# tinyarduinoschematic.net
KiCad netlist of a schematic drawn in Altium Designer
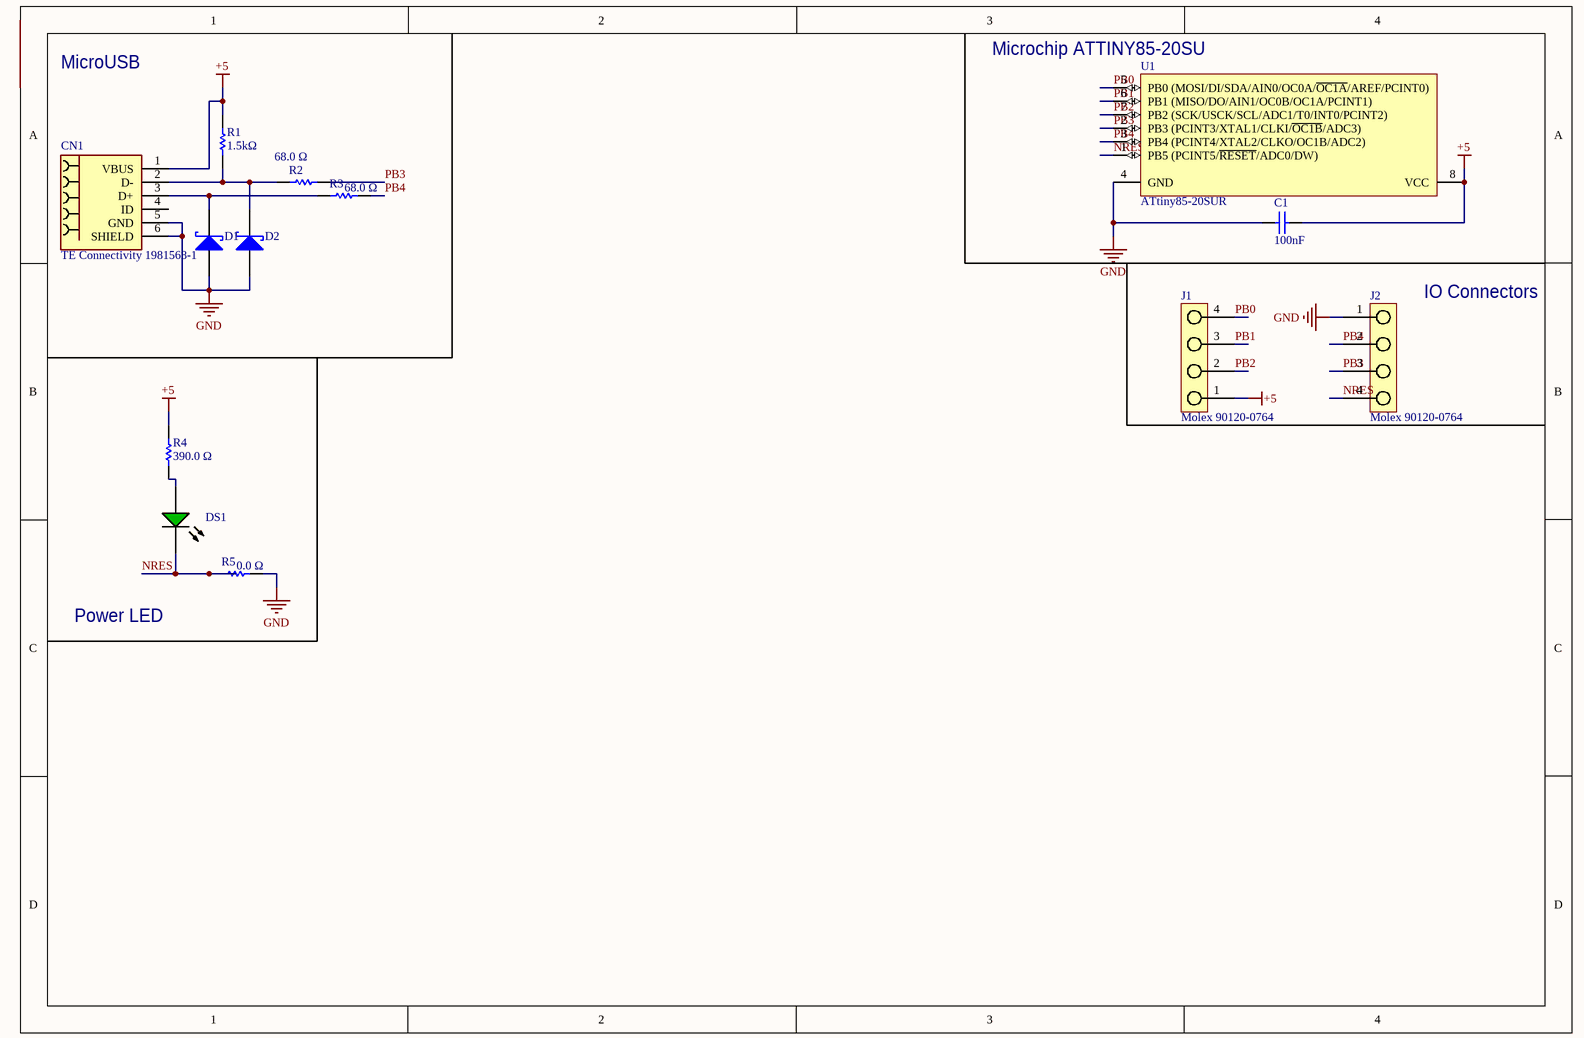
[diagram p0: tinyarduinoschematic.SchDoc]

(export (version "E")
  (design (tool "Eeschema 10.0.6"))
  (components
    (comp (ref "C1")
      (value "Cap")
      (footprint "PCB-cpn3sq1sqkb7wcygmy3s-1")
      (description "CAP CER 0.1UF 25V X7R 0603")
      (fields
        (field (name "CAPACITANCE") "100nF")
        (field (name "TOLERANCE") "±10%")
        (field (name "MANUFACTURER PART NUMBER") "06033C104KAT2A")
      )
      (libsource (lib "CommunityVault") (part "CMP-126693-6"))
    )
    (comp (ref "CN1")
      (value "TE Connectivity 1981568-1")
      (footprint "PCB-flraprbq3lplkrvccqj1-1")
      (description "Conn Micro USB 2.0 Type B RCP 5 POS 0.65mm Solder RA SMD 5 Terminal 1 Port T/R")
      (fields (field (name "MANUFACTURER PART NUMBER") "1981568-1"))
      (libsource (lib "CommunityVault") (part "CMP-c4780fb744281bbf-1"))
    )
    (comp (ref "D1")
      (value "Diodes Inc. B0540WS-7")
      (footprint "PCB-6tqbiewd2diqb4h5r69p-1")
      (description "B0540WS Series 40 V 0.5 A Schottky Barrier Rectifier Surface Mount - SOD-323")
      (fields (field (name "MANUFACTURER PART NUMBER") "B0540WS-7"))
      (libsource (lib "CommunityVault") (part "CMP-992e5020441546e9-1"))
    )
    (comp (ref "D2")
      (value "Diodes Inc. B0540WS-7")
      (footprint "PCB-6tqbiewd2diqb4h5r69p-1")
      (description "B0540WS Series 40 V 0.5 A Schottky Barrier Rectifier Surface Mount - SOD-323")
      (fields (field (name "MANUFACTURER PART NUMBER") "B0540WS-7"))
      (libsource (lib "CommunityVault") (part "CMP-992e5020441546e9-1"))
    )
    (comp (ref "DS1")
      (value "Avago HSMG-C190")
      (footprint "AVAG-HSMX-C190")
      (description "LED 570NM GREEN DIFF 0603 SMD")
      (libsource (lib "CommunityVault") (part "CMP-1544977-3"))
    )
    (comp (ref "J1")
      (value "Molex 90120-0764")
      (footprint "PCB-mruwntkvy73mrw75dg9m-1")
      (fields (field (name "MANUFACTURER PART NUMBER") "90120-0764"))
      (libsource (lib "") (part "SYM-f5c93cc9d0ed2a0e-2_1"))
    )
    (comp (ref "J2")
      (value "Molex 90120-0764")
      (footprint "PCB-mruwntkvy73mrw75dg9m-1")
      (fields (field (name "MANUFACTURER PART NUMBER") "90120-0764"))
      (libsource (lib "Octopart library") (part "SYM-f5c93cc9d0ed2a0e-2"))
    )
    (comp (ref "R1")
      (value "Vishay Dale CRCW06031K50JNEA")
      (footprint "RESC1609X50X30LL10T20")
      (description "RES SMD 1.5K OHM 5% 1/10W 0603")
      (fields (field (name "RESISTANCE") "1.5kΩ"))
      (libsource (lib "CommunityVault") (part "CMP-1856103-2"))
    )
    (comp (ref "R2")
      (value "Vishay Dale CRCW060368R0JNEA")
      (footprint "RESC1609X50X30ML10T20")
      (description "RES SMD 68 OHM 5% 1/10W 0603")
      (fields (field (name "RESISTANCE") "68.0 Ω"))
      (libsource (lib "CommunityVault") (part "CMP-1866767-2"))
    )
    (comp (ref "R3")
      (value "Vishay Dale CRCW060368R0JNEA")
      (footprint "RESC1609X50X30ML10T20")
      (description "RES SMD 68 OHM 5% 1/10W 0603")
      (fields (field (name "RESISTANCE") "68.0 Ω"))
      (libsource (lib "CommunityVault") (part "CMP-1866767-2"))
    )
    (comp (ref "R4")
      (value "Vishay Dale CRCW0603390RFKEA")
      (footprint "RESC1609X50X30LL10T20")
      (description "RES SMD 390 OHM 1% 1/10W 0603")
      (fields (field (name "RESISTANCE") "390.0 Ω"))
      (libsource (lib "CommunityVault") (part "CMP-3855866-2"))
    )
    (comp (ref "R5")
      (value "Vishay Dale CRCW06030000Z0EB")
      (footprint "RESC1609X50X30LL10T20")
      (description "Thick Film Resistors - SMD 1/10watt ZEROohm Jumper")
      (fields (field (name "RESISTANCE") "0.0 Ω"))
      (libsource (lib "CommunityVault") (part "CMP-1906891-2"))
    )
    (comp (ref "U1")
      (value "ATtiny85-20SUR")
      (footprint "8S2_L")
      (libsource (lib "Octopart library") (part "MC-8B-ATT25-IL8"))
    )
  )
  (nets
    (net (code "1") (name "+5") (class "Default")
      (node (ref "C1") (pin "1") (pinfunction "1_1") (pintype "passive"))
      (node (ref "CN1") (pin "1") (pinfunction "VBUS_1") (pintype "passive"))
      (node (ref "J1") (pin "1") (pinfunction "1_1") (pintype "passive"))
      (node (ref "R1") (pin "2") (pinfunction "2_2") (pintype "passive"))
      (node (ref "R4") (pin "2") (pinfunction "2_2") (pintype "passive"))
      (node (ref "U1") (pin "8") (pinfunction "VCC_8") (pintype "power_in"))
    )
    (net (code "2") (name "/NRES") (class "Default")
      (node (ref "DS1") (pin "2") (pinfunction "K_2") (pintype "passive"))
      (node (ref "J2") (pin "4") (pinfunction "4_4") (pintype "passive"))
      (node (ref "R5") (pin "1") (pinfunction "1_1") (pintype "passive"))
      (node (ref "U1") (pin "1") (pinfunction "PB5_(PCINT5/~{RESET}/ADC0/DW)_1") (pintype "bidirectional"))
    )
    (net (code "3") (name "/PB0") (class "Default")
      (node (ref "J1") (pin "4") (pinfunction "4_4") (pintype "passive"))
      (node (ref "U1") (pin "5") (pinfunction "PB0_(MOSI/DI/SDA/AIN0/OC0A/~{OC1A}/AREF/PCINT0)_5") (pintype "bidirectional"))
    )
    (net (code "4") (name "/PB1") (class "Default")
      (node (ref "J1") (pin "3") (pinfunction "3_3") (pintype "passive"))
      (node (ref "U1") (pin "6") (pinfunction "PB1_(MISO/DO/AIN1/OC0B/OC1A/PCINT1)_6") (pintype "bidirectional"))
    )
    (net (code "5") (name "/PB2") (class "Default")
      (node (ref "J1") (pin "2") (pinfunction "2_2") (pintype "passive"))
      (node (ref "U1") (pin "7") (pinfunction "PB2_(SCK/USCK/SCL/ADC1/T0/INT0/PCINT2)_7") (pintype "bidirectional"))
    )
    (net (code "6") (name "/PB3") (class "Default")
      (node (ref "J2") (pin "3") (pinfunction "3_3") (pintype "passive"))
      (node (ref "R2") (pin "2") (pinfunction "2_2") (pintype "passive"))
      (node (ref "U1") (pin "2") (pinfunction "PB3_(PCINT3/XTAL1/CLKI/~{OC1B}/ADC3)_2") (pintype "bidirectional"))
    )
    (net (code "7") (name "/PB4") (class "Default")
      (node (ref "J2") (pin "2") (pinfunction "2_2") (pintype "passive"))
      (node (ref "R3") (pin "2") (pinfunction "2_2") (pintype "passive"))
      (node (ref "U1") (pin "3") (pinfunction "PB4_(PCINT4/XTAL2/CLKO/OC1B/ADC2)_3") (pintype "bidirectional"))
    )
    (net (code "8") (name "GND") (class "Default")
      (node (ref "C1") (pin "2") (pinfunction "2_2") (pintype "passive"))
      (node (ref "CN1") (pin "5") (pinfunction "GND_5") (pintype "passive"))
      (node (ref "CN1") (pin "6") (pinfunction "SHIELD_6") (pintype "passive"))
      (node (ref "D1") (pin "2") (pinfunction "A_2") (pintype "passive"))
      (node (ref "D2") (pin "2") (pinfunction "A_2") (pintype "passive"))
      (node (ref "J2") (pin "1") (pinfunction "1_1") (pintype "passive"))
      (node (ref "R5") (pin "2") (pinfunction "2_2") (pintype "passive"))
      (node (ref "U1") (pin "4") (pinfunction "GND_4") (pintype "power_in"))
    )
    (net (code "9") (name "Net-(CN1-D+)") (class "Default")
      (node (ref "CN1") (pin "3") (pinfunction "D+_3") (pintype "passive"))
      (node (ref "D1") (pin "1") (pinfunction "K_1") (pintype "passive"))
      (node (ref "R3") (pin "1") (pinfunction "1_1") (pintype "passive"))
    )
    (net (code "10") (name "Net-(CN1-D-)") (class "Default")
      (node (ref "CN1") (pin "2") (pinfunction "D-_2") (pintype "passive"))
      (node (ref "D2") (pin "1") (pinfunction "K_1") (pintype "passive"))
      (node (ref "R1") (pin "1") (pinfunction "1_1") (pintype "passive"))
      (node (ref "R2") (pin "1") (pinfunction "1_1") (pintype "passive"))
    )
    (net (code "11") (name "Net-(DS1-A)") (class "Default")
      (node (ref "DS1") (pin "1") (pinfunction "A_1") (pintype "passive"))
      (node (ref "R4") (pin "1") (pinfunction "1_1") (pintype "passive"))
    )
    (net (code "12") (name "unconnected-(CN1-ID-Pad4)") (class "Default")
      (node (ref "CN1") (pin "4") (pinfunction "ID_4") (pintype "passive"))
    )
  )
)
